# SHIELD.net
KiCad netlist of a schematic drawn in EAGLE
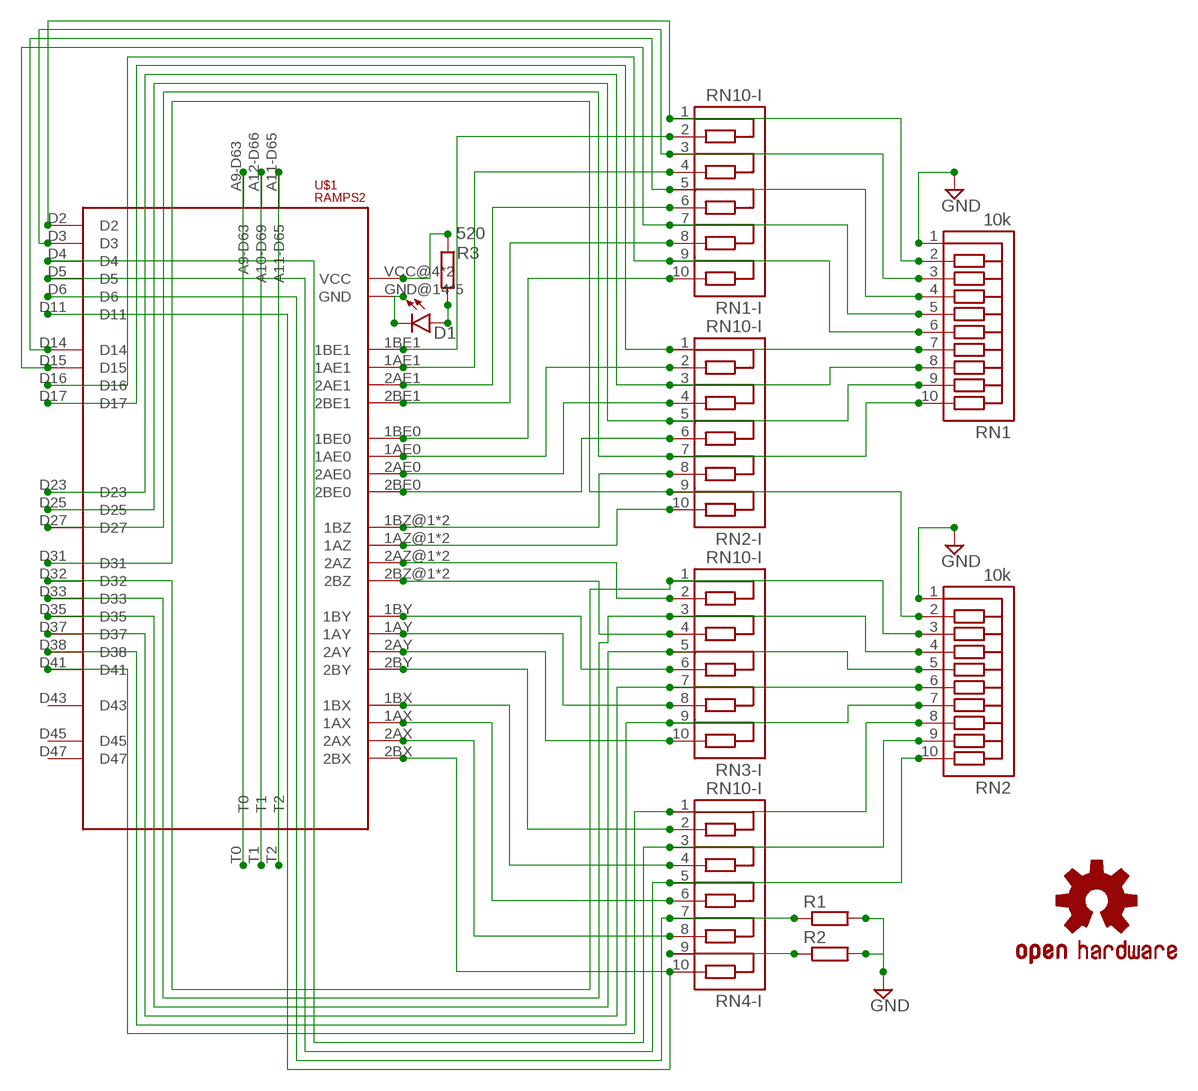
[diagram p0: schematic, sheet 1]

(export (version "E")
  (design (tool "Eeschema 10.0.6"))
  (components
    (comp (ref "D1")
      (value "LED-3MM-NO_SILK")
      (footprint "eagle-import:LED3MM-NS")
      (libsource (lib "eagle-import") (part "LED-3MM-NO_SILK"))
    )
    (comp (ref "LOGO2")
      (value "OSHW-LOGOL-COPPER")
      (footprint "eagle-import:OSHW-LOGO-L_COPPER")
      (libsource (lib "eagle-import") (part "OSHW-LOGOL-COPPER"))
    )
    (comp (ref "R1")
      (value "R-EU_0204/7")
      (footprint "eagle-import:0204_7")
      (libsource (lib "eagle-import") (part "R-EU_0204/7"))
    )
    (comp (ref "R2")
      (value "R-EU_0204/7")
      (footprint "eagle-import:0204_7")
      (libsource (lib "eagle-import") (part "R-EU_0204/7"))
    )
    (comp (ref "R3")
      (value "520")
      (footprint "eagle-import:0204_7")
      (libsource (lib "eagle-import") (part "R-EU_0204/7"))
    )
    (comp (ref "RN1")
      (value "10k")
      (footprint "eagle-import:RN10")
      (libsource (lib "eagle-import") (part "RN10"))
    )
    (comp (ref "RN1-I")
      (value "RN10-I")
      (footprint "eagle-import:RN10")
      (libsource (lib "eagle-import") (part "RN10-I"))
    )
    (comp (ref "RN2")
      (value "10k")
      (footprint "eagle-import:RN10")
      (libsource (lib "eagle-import") (part "RN10"))
    )
    (comp (ref "RN2-I")
      (value "RN10-I")
      (footprint "eagle-import:RN10")
      (libsource (lib "eagle-import") (part "RN10-I"))
    )
    (comp (ref "RN3-I")
      (value "RN10-I")
      (footprint "eagle-import:RN10")
      (libsource (lib "eagle-import") (part "RN10-I"))
    )
    (comp (ref "RN4-I")
      (value "RN10-I")
      (footprint "eagle-import:RN10")
      (libsource (lib "eagle-import") (part "RN10-I"))
    )
    (comp (ref "U$1")
      (value "RAMPS2")
      (footprint "eagle-import:RAMPS2")
      (libsource (lib "eagle-import") (part "RAMPS2"))
    )
  )
  (nets
    (net (code "1") (name "GND") (class "Default")
      (node (ref "R1") (pin "2") (pinfunction "2_2") (pintype "passive"))
      (node (ref "R2") (pin "2") (pinfunction "2_2") (pintype "passive"))
      (node (ref "RN1") (pin "1") (pinfunction "1_1") (pintype "passive"))
      (node (ref "RN2") (pin "1") (pinfunction "1_1") (pintype "passive"))
    )
    (net (code "2") (name "Net-(D1-C)") (class "Default")
      (node (ref "D1") (pin "K") (pinfunction "C_K") (pintype "passive"))
      (node (ref "U$1") (pin "GND@14") (pinfunction "GND_GND@14") (pintype "power_in"))
      (node (ref "U$1") (pin "GND@16") (pinfunction "GND_GND@16") (pintype "power_in"))
      (node (ref "U$1") (pin "GND@17") (pinfunction "GND_GND@17") (pintype "power_in"))
      (node (ref "U$1") (pin "GND@18") (pinfunction "GND_GND@18") (pintype "power_in"))
      (node (ref "U$1") (pin "GND@19") (pinfunction "GND_GND@19") (pintype "power_in"))
    )
    (net (code "3") (name "Net-(D1-PadA)") (class "Default")
      (node (ref "D1") (pin "A") (pinfunction "A_A") (pintype "passive"))
      (node (ref "R3") (pin "2") (pinfunction "2_2") (pintype "passive"))
    )
    (net (code "4") (name "Net-(R1-Pad1)") (class "Default")
      (node (ref "R1") (pin "1") (pinfunction "1_1") (pintype "passive"))
      (node (ref "RN4-I") (pin "7") (pinfunction "7_7") (pintype "passive"))
      (node (ref "U$1") (pin "D6") (pinfunction "D6_D6") (pintype "bidirectional"))
    )
    (net (code "5") (name "Net-(R2-Pad1)") (class "Default")
      (node (ref "R2") (pin "1") (pinfunction "1_1") (pintype "passive"))
      (node (ref "RN4-I") (pin "9") (pinfunction "9_9") (pintype "passive"))
    )
    (net (code "6") (name "Net-(R3-Pad1)") (class "Default")
      (node (ref "R3") (pin "1") (pinfunction "1_1") (pintype "passive"))
      (node (ref "U$1") (pin "VCC@4") (pinfunction "VCC_VCC@4") (pintype "power_in"))
      (node (ref "U$1") (pin "VCC@6") (pinfunction "VCC_VCC@6") (pintype "power_in"))
    )
    (net (code "7") (name "Net-(RN1-I-Pad1)") (class "Default")
      (node (ref "RN1") (pin "2") (pinfunction "2_2") (pintype "passive"))
      (node (ref "RN1-I") (pin "1") (pinfunction "1_1") (pintype "passive"))
      (node (ref "U$1") (pin "D2") (pinfunction "D2_D2") (pintype "bidirectional"))
    )
    (net (code "8") (name "Net-(RN1-I-Pad2)") (class "Default")
      (node (ref "RN1-I") (pin "2") (pinfunction "2_2") (pintype "passive"))
      (node (ref "U$1") (pin "1BE1") (pinfunction "1BE1_1BE1") (pintype "bidirectional"))
    )
    (net (code "9") (name "Net-(RN1-I-Pad3)") (class "Default")
      (node (ref "RN1") (pin "3") (pinfunction "3_3") (pintype "passive"))
      (node (ref "RN1-I") (pin "3") (pinfunction "3_3") (pintype "passive"))
      (node (ref "U$1") (pin "D3") (pinfunction "D3_D3") (pintype "bidirectional"))
    )
    (net (code "10") (name "Net-(RN1-I-Pad4)") (class "Default")
      (node (ref "RN1-I") (pin "4") (pinfunction "4_4") (pintype "passive"))
      (node (ref "U$1") (pin "1AE1") (pinfunction "1AE1_1AE1") (pintype "bidirectional"))
    )
    (net (code "11") (name "Net-(RN1-I-Pad5)") (class "Default")
      (node (ref "RN1") (pin "4") (pinfunction "4_4") (pintype "passive"))
      (node (ref "RN1-I") (pin "5") (pinfunction "5_5") (pintype "passive"))
      (node (ref "U$1") (pin "D14") (pinfunction "D14_D14") (pintype "bidirectional"))
    )
    (net (code "12") (name "Net-(RN1-I-Pad6)") (class "Default")
      (node (ref "RN1-I") (pin "6") (pinfunction "6_6") (pintype "passive"))
      (node (ref "U$1") (pin "2AE1") (pinfunction "2AE1_2AE1") (pintype "bidirectional"))
    )
    (net (code "13") (name "Net-(RN1-I-Pad7)") (class "Default")
      (node (ref "RN1") (pin "5") (pinfunction "5_5") (pintype "passive"))
      (node (ref "RN1-I") (pin "7") (pinfunction "7_7") (pintype "passive"))
      (node (ref "U$1") (pin "D15") (pinfunction "D15_D15") (pintype "bidirectional"))
    )
    (net (code "14") (name "Net-(RN1-I-Pad8)") (class "Default")
      (node (ref "RN1-I") (pin "8") (pinfunction "8_8") (pintype "passive"))
      (node (ref "U$1") (pin "2BE1") (pinfunction "2BE1_2BE1") (pintype "bidirectional"))
    )
    (net (code "15") (name "Net-(RN1-I-Pad9)") (class "Default")
      (node (ref "RN1") (pin "6") (pinfunction "6_6") (pintype "passive"))
      (node (ref "RN1-I") (pin "9") (pinfunction "9_9") (pintype "passive"))
      (node (ref "U$1") (pin "D16") (pinfunction "D16_D16") (pintype "bidirectional"))
    )
    (net (code "16") (name "Net-(RN1-I-Pad10)") (class "Default")
      (node (ref "RN1-I") (pin "10") (pinfunction "10_10") (pintype "passive"))
      (node (ref "U$1") (pin "1BE0") (pinfunction "1BE0_1BE0") (pintype "bidirectional"))
    )
    (net (code "17") (name "Net-(RN1-Pad7)") (class "Default")
      (node (ref "RN1") (pin "7") (pinfunction "7_7") (pintype "passive"))
      (node (ref "RN2-I") (pin "1") (pinfunction "1_1") (pintype "passive"))
      (node (ref "U$1") (pin "D17") (pinfunction "D17_D17") (pintype "bidirectional"))
    )
    (net (code "18") (name "Net-(RN1-Pad8)") (class "Default")
      (node (ref "RN1") (pin "8") (pinfunction "8_8") (pintype "passive"))
      (node (ref "RN2-I") (pin "3") (pinfunction "3_3") (pintype "passive"))
      (node (ref "U$1") (pin "D23") (pinfunction "D23_D23") (pintype "bidirectional"))
    )
    (net (code "19") (name "Net-(RN1-Pad9)") (class "Default")
      (node (ref "RN1") (pin "9") (pinfunction "9_9") (pintype "passive"))
      (node (ref "RN2-I") (pin "5") (pinfunction "5_5") (pintype "passive"))
      (node (ref "U$1") (pin "D25") (pinfunction "D25_D25") (pintype "bidirectional"))
    )
    (net (code "20") (name "Net-(RN1-Pad10)") (class "Default")
      (node (ref "RN1") (pin "10") (pinfunction "10_10") (pintype "passive"))
      (node (ref "RN2-I") (pin "7") (pinfunction "7_7") (pintype "passive"))
      (node (ref "U$1") (pin "D27") (pinfunction "D27_D27") (pintype "bidirectional"))
    )
    (net (code "21") (name "Net-(RN2-I-Pad2)") (class "Default")
      (node (ref "RN2-I") (pin "2") (pinfunction "2_2") (pintype "passive"))
      (node (ref "U$1") (pin "1AE0") (pinfunction "1AE0_1AE0") (pintype "bidirectional"))
    )
    (net (code "22") (name "Net-(RN2-I-Pad4)") (class "Default")
      (node (ref "RN2-I") (pin "4") (pinfunction "4_4") (pintype "passive"))
      (node (ref "U$1") (pin "2AE0") (pinfunction "2AE0_2AE0") (pintype "bidirectional"))
    )
    (net (code "23") (name "Net-(RN2-I-Pad6)") (class "Default")
      (node (ref "RN2-I") (pin "6") (pinfunction "6_6") (pintype "passive"))
      (node (ref "U$1") (pin "2BE0") (pinfunction "2BE0_2BE0") (pintype "bidirectional"))
    )
    (net (code "24") (name "Net-(RN2-I-Pad8)") (class "Default")
      (node (ref "RN2-I") (pin "8") (pinfunction "8_8") (pintype "passive"))
      (node (ref "U$1") (pin "1BZ@1") (pinfunction "1BZ_1BZ@1") (pintype "bidirectional"))
      (node (ref "U$1") (pin "1BZ@2") (pinfunction "1BZ_1BZ@2") (pintype "bidirectional"))
    )
    (net (code "25") (name "Net-(RN2-I-Pad9)") (class "Default")
      (node (ref "RN2") (pin "2") (pinfunction "2_2") (pintype "passive"))
      (node (ref "RN2-I") (pin "9") (pinfunction "9_9") (pintype "passive"))
      (node (ref "U$1") (pin "D31") (pinfunction "D31_D31") (pintype "bidirectional"))
    )
    (net (code "26") (name "Net-(RN2-I-Pad10)") (class "Default")
      (node (ref "RN2-I") (pin "10") (pinfunction "10_10") (pintype "passive"))
      (node (ref "U$1") (pin "1AZ@1") (pinfunction "1AZ_1AZ@1") (pintype "bidirectional"))
      (node (ref "U$1") (pin "1AZ@2") (pinfunction "1AZ_1AZ@2") (pintype "bidirectional"))
    )
    (net (code "27") (name "Net-(RN2-Pad3)") (class "Default")
      (node (ref "RN2") (pin "3") (pinfunction "3_3") (pintype "passive"))
      (node (ref "RN3-I") (pin "1") (pinfunction "1_1") (pintype "passive"))
      (node (ref "U$1") (pin "D32") (pinfunction "D32_D32") (pintype "bidirectional"))
    )
    (net (code "28") (name "Net-(RN2-Pad4)") (class "Default")
      (node (ref "RN2") (pin "4") (pinfunction "4_4") (pintype "passive"))
      (node (ref "RN3-I") (pin "3") (pinfunction "3_3") (pintype "passive"))
      (node (ref "U$1") (pin "D33") (pinfunction "D33_D33") (pintype "input"))
    )
    (net (code "29") (name "Net-(RN2-Pad5)") (class "Default")
      (node (ref "RN2") (pin "5") (pinfunction "5_5") (pintype "passive"))
      (node (ref "RN3-I") (pin "5") (pinfunction "5_5") (pintype "passive"))
      (node (ref "U$1") (pin "D35") (pinfunction "D35_D35") (pintype "bidirectional"))
    )
    (net (code "30") (name "Net-(RN2-Pad6)") (class "Default")
      (node (ref "RN2") (pin "6") (pinfunction "6_6") (pintype "passive"))
      (node (ref "RN3-I") (pin "7") (pinfunction "7_7") (pintype "passive"))
      (node (ref "U$1") (pin "D37") (pinfunction "D37_D37") (pintype "bidirectional"))
    )
    (net (code "31") (name "Net-(RN2-Pad7)") (class "Default")
      (node (ref "RN2") (pin "7") (pinfunction "7_7") (pintype "passive"))
      (node (ref "RN3-I") (pin "9") (pinfunction "9_9") (pintype "passive"))
      (node (ref "U$1") (pin "D38") (pinfunction "D38_D38") (pintype "bidirectional"))
    )
    (net (code "32") (name "Net-(RN2-Pad8)") (class "Default")
      (node (ref "RN2") (pin "8") (pinfunction "8_8") (pintype "passive"))
      (node (ref "RN4-I") (pin "1") (pinfunction "1_1") (pintype "passive"))
      (node (ref "U$1") (pin "D41") (pinfunction "D41_D41") (pintype "bidirectional"))
    )
    (net (code "33") (name "Net-(RN2-Pad9)") (class "Default")
      (node (ref "RN2") (pin "9") (pinfunction "9_9") (pintype "passive"))
      (node (ref "RN4-I") (pin "3") (pinfunction "3_3") (pintype "passive"))
      (node (ref "U$1") (pin "D4") (pinfunction "D4_D4") (pintype "bidirectional"))
    )
    (net (code "34") (name "Net-(RN2-Pad10)") (class "Default")
      (node (ref "RN2") (pin "10") (pinfunction "10_10") (pintype "passive"))
      (node (ref "RN4-I") (pin "5") (pinfunction "5_5") (pintype "passive"))
      (node (ref "U$1") (pin "D5") (pinfunction "D5_D5") (pintype "bidirectional"))
    )
    (net (code "35") (name "Net-(RN3-I-Pad2)") (class "Default")
      (node (ref "RN3-I") (pin "2") (pinfunction "2_2") (pintype "passive"))
      (node (ref "U$1") (pin "2AZ@1") (pinfunction "2AZ_2AZ@1") (pintype "bidirectional"))
      (node (ref "U$1") (pin "2AZ@2") (pinfunction "2AZ_2AZ@2") (pintype "bidirectional"))
    )
    (net (code "36") (name "Net-(RN3-I-Pad4)") (class "Default")
      (node (ref "RN3-I") (pin "4") (pinfunction "4_4") (pintype "passive"))
      (node (ref "U$1") (pin "2BZ@1") (pinfunction "2BZ_2BZ@1") (pintype "bidirectional"))
      (node (ref "U$1") (pin "2BZ@2") (pinfunction "2BZ_2BZ@2") (pintype "bidirectional"))
    )
    (net (code "37") (name "Net-(RN3-I-Pad6)") (class "Default")
      (node (ref "RN3-I") (pin "6") (pinfunction "6_6") (pintype "passive"))
      (node (ref "U$1") (pin "1BY") (pinfunction "1BY_1BY") (pintype "bidirectional"))
    )
    (net (code "38") (name "Net-(RN3-I-Pad8)") (class "Default")
      (node (ref "RN3-I") (pin "8") (pinfunction "8_8") (pintype "passive"))
      (node (ref "U$1") (pin "1AY") (pinfunction "1AY_1AY") (pintype "bidirectional"))
    )
    (net (code "39") (name "Net-(RN3-I-Pad10)") (class "Default")
      (node (ref "RN3-I") (pin "10") (pinfunction "10_10") (pintype "passive"))
      (node (ref "U$1") (pin "2AY") (pinfunction "2AY_2AY") (pintype "bidirectional"))
    )
    (net (code "40") (name "Net-(RN4-I-Pad2)") (class "Default")
      (node (ref "RN4-I") (pin "2") (pinfunction "2_2") (pintype "passive"))
      (node (ref "U$1") (pin "2BY") (pinfunction "2BY_2BY") (pintype "bidirectional"))
    )
    (net (code "41") (name "Net-(RN4-I-Pad4)") (class "Default")
      (node (ref "RN4-I") (pin "4") (pinfunction "4_4") (pintype "passive"))
      (node (ref "U$1") (pin "1BX") (pinfunction "1BX_1BX") (pintype "bidirectional"))
    )
    (net (code "42") (name "Net-(RN4-I-Pad6)") (class "Default")
      (node (ref "RN4-I") (pin "6") (pinfunction "6_6") (pintype "passive"))
      (node (ref "U$1") (pin "1AX") (pinfunction "1AX_1AX") (pintype "bidirectional"))
    )
    (net (code "43") (name "Net-(RN4-I-Pad8)") (class "Default")
      (node (ref "RN4-I") (pin "8") (pinfunction "8_8") (pintype "passive"))
      (node (ref "U$1") (pin "2AX") (pinfunction "2AX_2AX") (pintype "bidirectional"))
    )
    (net (code "44") (name "Net-(RN4-I-Pad10)") (class "Default")
      (node (ref "RN4-I") (pin "10") (pinfunction "10_10") (pintype "passive"))
      (node (ref "U$1") (pin "2BX") (pinfunction "2BX_2BX") (pintype "bidirectional"))
      (node (ref "U$1") (pin "D11") (pinfunction "D11_D11") (pintype "bidirectional"))
    )
    (net (code "45") (name "Net-(U$1-A10-D69)") (class "Default")
      (node (ref "U$1") (pin "A12-D66") (pinfunction "A10-D69_A12-D66") (pintype "bidirectional"))
      (node (ref "U$1") (pin "T1") (pinfunction "T1_T1") (pintype "bidirectional"))
    )
    (net (code "46") (name "Net-(U$1-PadA9-D63)") (class "Default")
      (node (ref "U$1") (pin "A9-D63") (pinfunction "A9-D63_A9-D63") (pintype "bidirectional"))
      (node (ref "U$1") (pin "T0") (pinfunction "T0_T0") (pintype "bidirectional"))
    )
    (net (code "47") (name "Net-(U$1-PadA11-D65)") (class "Default")
      (node (ref "U$1") (pin "A11-D65") (pinfunction "A11-D65_A11-D65") (pintype "bidirectional"))
      (node (ref "U$1") (pin "T2") (pinfunction "T2_T2") (pintype "bidirectional"))
    )
    (net (code "48") (name "unconnected-(U$1-PadD43)") (class "Default")
      (node (ref "U$1") (pin "D43") (pinfunction "D43_D43") (pintype "bidirectional"))
    )
    (net (code "49") (name "unconnected-(U$1-PadD45)") (class "Default")
      (node (ref "U$1") (pin "D45") (pinfunction "D45_D45") (pintype "bidirectional"))
    )
    (net (code "50") (name "unconnected-(U$1-PadD47)") (class "Default")
      (node (ref "U$1") (pin "D47") (pinfunction "D47_D47") (pintype "bidirectional"))
    )
  )
)
